# BNO055_MS5838BoB_v02.net
KiCad netlist of a schematic drawn in EAGLE
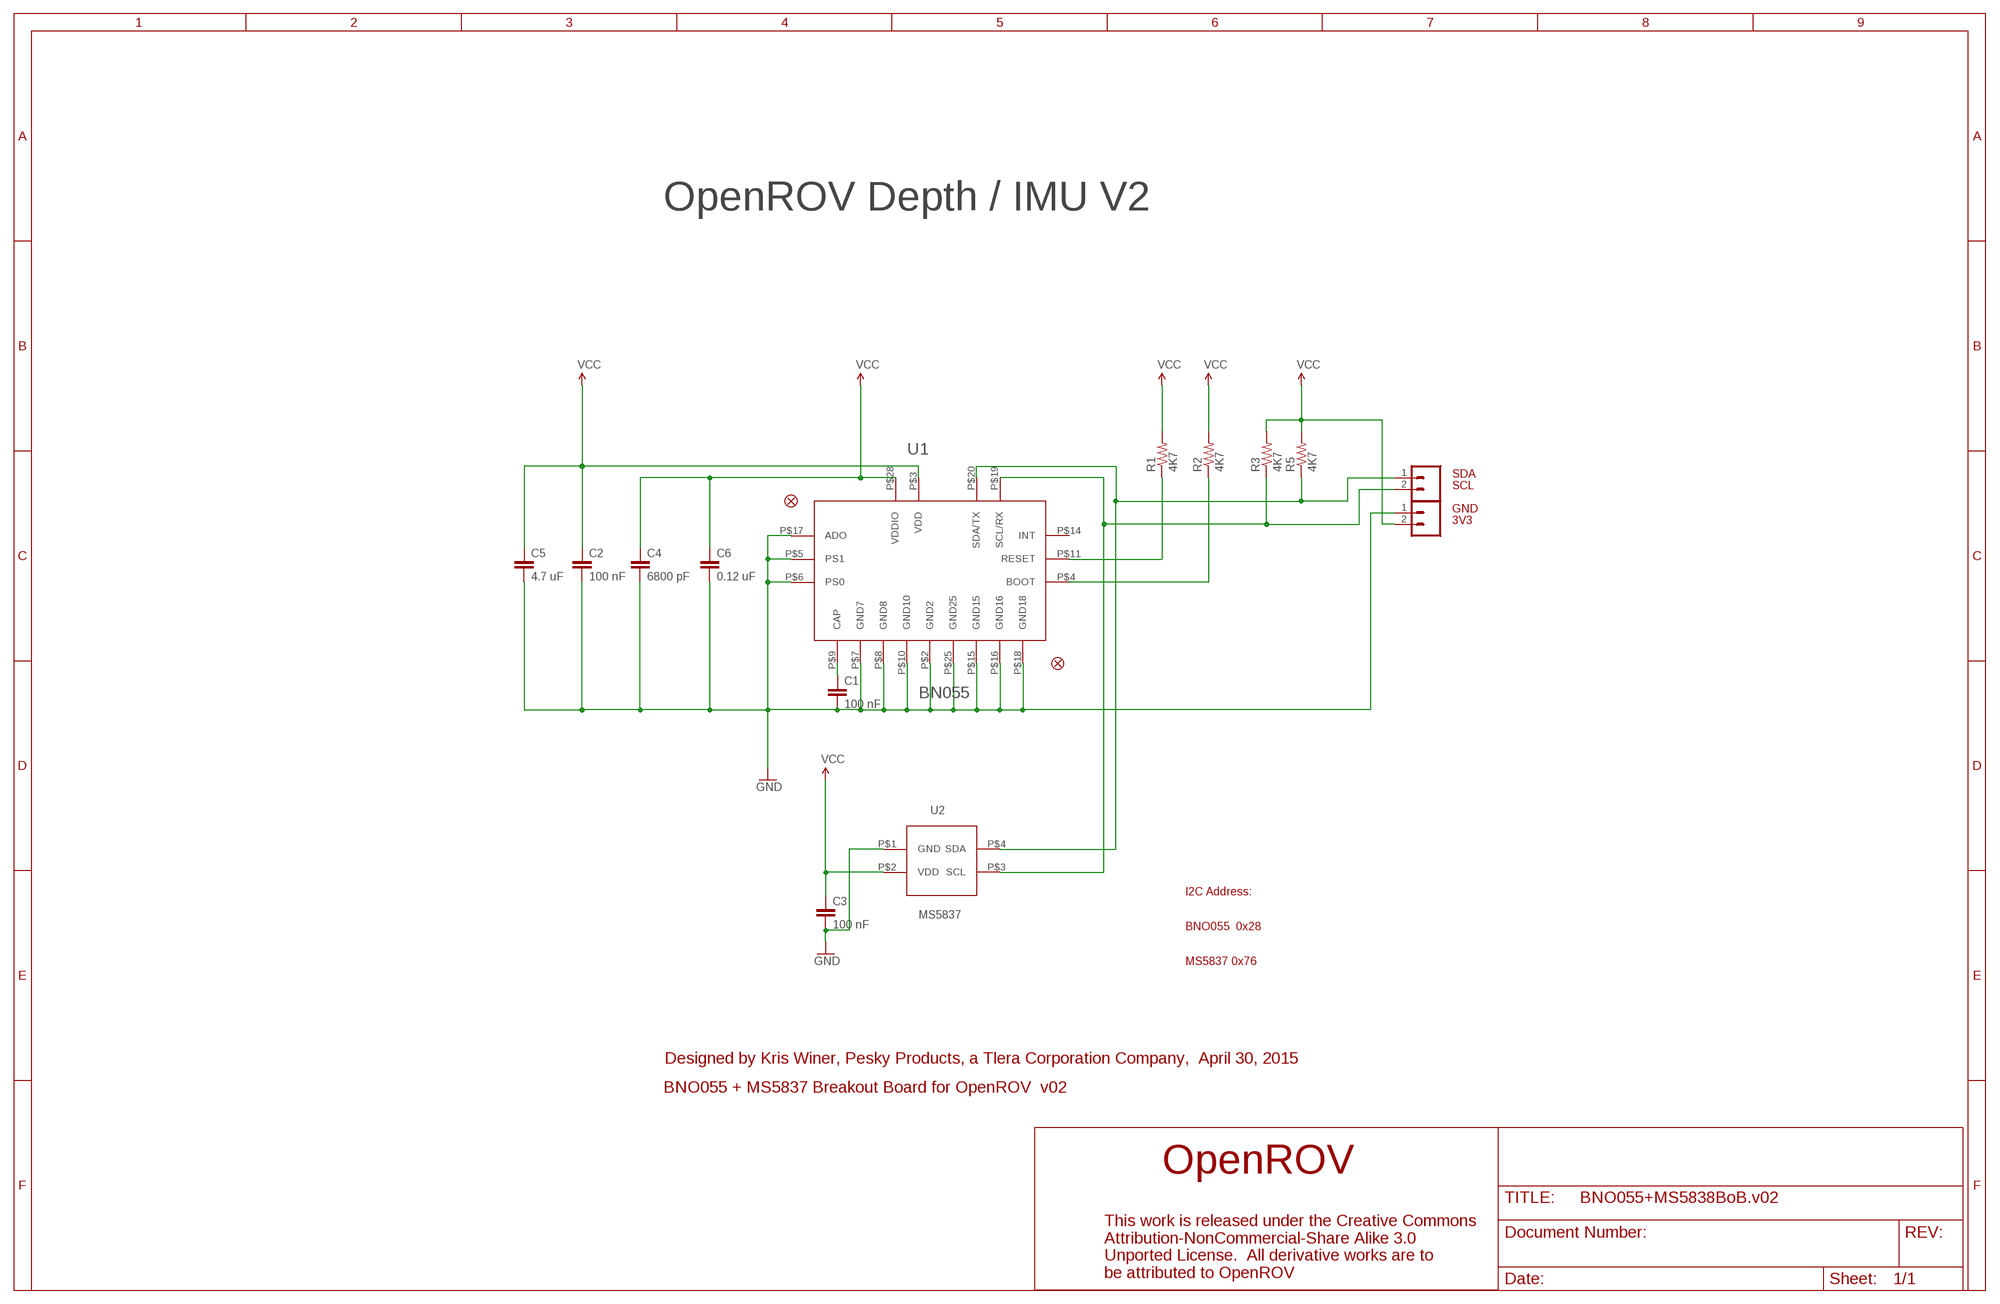
[diagram p0: schematic, sheet 1]

(export (version "E")
  (design (tool "Eeschema 10.0.6"))
  (components
    (comp (ref "C1")
      (value "100 nF")
      (footprint "eagle-import:C0402")
      (libsource (lib "eagle-import") (part "C-EUC0402"))
    )
    (comp (ref "C2")
      (value "100 nF")
      (footprint "eagle-import:C0402")
      (libsource (lib "eagle-import") (part "C-EUC0402"))
    )
    (comp (ref "C3")
      (value "100 nF")
      (footprint "eagle-import:C0402")
      (libsource (lib "eagle-import") (part "C-EUC0402"))
    )
    (comp (ref "C4")
      (value "6800 pF")
      (footprint "eagle-import:C0402")
      (libsource (lib "eagle-import") (part "C-EUC0402"))
    )
    (comp (ref "C5")
      (value "4.7 uF")
      (footprint "eagle-import:C0402")
      (libsource (lib "eagle-import") (part "C-EUC0402"))
    )
    (comp (ref "C6")
      (value "0.12 uF")
      (footprint "eagle-import:C0402")
      (libsource (lib "eagle-import") (part "C-EUC0402"))
    )
    (comp (ref "FID1")
      (value "FIDUCIALUFIDUCIAL")
      (footprint "eagle-import:MICRO-FIDUCIAL")
      (libsource (lib "eagle-import") (part "FIDUCIALUFIDUCIAL"))
    )
    (comp (ref "FID2")
      (value "FIDUCIALUFIDUCIAL")
      (footprint "eagle-import:MICRO-FIDUCIAL")
      (libsource (lib "eagle-import") (part "FIDUCIALUFIDUCIAL"))
    )
    (comp (ref "JP2")
      (value "M021X02_NO_SILK")
      (footprint "eagle-import:1X02_NO_SILK")
      (libsource (lib "eagle-import") (part "M021X02_NO_SILK"))
    )
    (comp (ref "JP3")
      (value "M021X02_NO_SILK")
      (footprint "eagle-import:1X02_NO_SILK")
      (libsource (lib "eagle-import") (part "M021X02_NO_SILK"))
    )
    (comp (ref "R1")
      (value "4K7")
      (footprint "eagle-import:R0402")
      (libsource (lib "eagle-import") (part "R-US_R0402"))
    )
    (comp (ref "R2")
      (value "4K7")
      (footprint "eagle-import:R0402")
      (libsource (lib "eagle-import") (part "R-US_R0402"))
    )
    (comp (ref "R3")
      (value "4K7")
      (footprint "eagle-import:R0402")
      (libsource (lib "eagle-import") (part "R-US_R0402"))
    )
    (comp (ref "R5")
      (value "4K7")
      (footprint "eagle-import:R0402")
      (libsource (lib "eagle-import") (part "R-US_R0402"))
    )
    (comp (ref "U1")
      (value "BN055")
      (footprint "eagle-import:LGA28")
      (libsource (lib "eagle-import") (part "BN055"))
    )
    (comp (ref "U2")
      (value "MS5837")
      (footprint "eagle-import:MS5837")
      (libsource (lib "eagle-import") (part "MS5837"))
    )
  )
  (nets
    (net (code "1") (name "GND") (class "Default")
      (node (ref "C1") (pin "2") (pinfunction "2_2") (pintype "passive"))
      (node (ref "C2") (pin "2") (pinfunction "2_2") (pintype "passive"))
      (node (ref "C3") (pin "2") (pinfunction "2_2") (pintype "passive"))
      (node (ref "C4") (pin "2") (pinfunction "2_2") (pintype "passive"))
      (node (ref "C5") (pin "2") (pinfunction "2_2") (pintype "passive"))
      (node (ref "C6") (pin "2") (pinfunction "2_2") (pintype "passive"))
      (node (ref "JP3") (pin "1") (pinfunction "1_1") (pintype "passive"))
      (node (ref "U1") (pin "P$10") (pinfunction "GND10_P$10") (pintype "power_in"))
      (node (ref "U1") (pin "P$15") (pinfunction "GND15_P$15") (pintype "power_in"))
      (node (ref "U1") (pin "P$16") (pinfunction "GND16_P$16") (pintype "power_in"))
      (node (ref "U1") (pin "P$17") (pinfunction "ADO_P$17") (pintype "bidirectional"))
      (node (ref "U1") (pin "P$18") (pinfunction "GND18_P$18") (pintype "power_in"))
      (node (ref "U1") (pin "P$2") (pinfunction "GND2_P$2") (pintype "power_in"))
      (node (ref "U1") (pin "P$25") (pinfunction "GND25_P$25") (pintype "power_in"))
      (node (ref "U1") (pin "P$5") (pinfunction "PS1_P$5") (pintype "bidirectional"))
      (node (ref "U1") (pin "P$6") (pinfunction "PS0_P$6") (pintype "bidirectional"))
      (node (ref "U1") (pin "P$7") (pinfunction "GND7_P$7") (pintype "power_in"))
      (node (ref "U1") (pin "P$8") (pinfunction "GND8_P$8") (pintype "power_in"))
      (node (ref "U2") (pin "P$1") (pinfunction "GND_P$1") (pintype "bidirectional"))
    )
    (net (code "2") (name "Net-(U1-BOOT)") (class "Default")
      (node (ref "R2") (pin "1") (pinfunction "1_1") (pintype "passive"))
      (node (ref "U1") (pin "P$4") (pinfunction "BOOT_P$4") (pintype "bidirectional"))
    )
    (net (code "3") (name "Net-(U1-CAP)") (class "Default")
      (node (ref "C1") (pin "1") (pinfunction "1_1") (pintype "passive"))
      (node (ref "U1") (pin "P$9") (pinfunction "CAP_P$9") (pintype "power_in"))
    )
    (net (code "4") (name "Net-(U1-RESET)") (class "Default")
      (node (ref "R1") (pin "1") (pinfunction "1_1") (pintype "passive"))
      (node (ref "U1") (pin "P$11") (pinfunction "RESET_P$11") (pintype "bidirectional"))
    )
    (net (code "5") (name "Net-(U1-SCL{slash}RX)") (class "Default")
      (node (ref "JP2") (pin "2") (pinfunction "2_2") (pintype "passive"))
      (node (ref "R3") (pin "1") (pinfunction "1_1") (pintype "passive"))
      (node (ref "U1") (pin "P$19") (pinfunction "SCL/RX_P$19") (pintype "bidirectional"))
      (node (ref "U2") (pin "P$3") (pinfunction "SCL_P$3") (pintype "bidirectional"))
    )
    (net (code "6") (name "Net-(U1-SDA{slash}TX)") (class "Default")
      (node (ref "JP2") (pin "1") (pinfunction "1_1") (pintype "passive"))
      (node (ref "R5") (pin "1") (pinfunction "1_1") (pintype "passive"))
      (node (ref "U1") (pin "P$20") (pinfunction "SDA/TX_P$20") (pintype "bidirectional"))
      (node (ref "U2") (pin "P$4") (pinfunction "SDA_P$4") (pintype "bidirectional"))
    )
    (net (code "7") (name "VCC") (class "Default")
      (node (ref "C2") (pin "1") (pinfunction "1_1") (pintype "passive"))
      (node (ref "C3") (pin "1") (pinfunction "1_1") (pintype "passive"))
      (node (ref "C4") (pin "1") (pinfunction "1_1") (pintype "passive"))
      (node (ref "C5") (pin "1") (pinfunction "1_1") (pintype "passive"))
      (node (ref "C6") (pin "1") (pinfunction "1_1") (pintype "passive"))
      (node (ref "JP3") (pin "2") (pinfunction "2_2") (pintype "passive"))
      (node (ref "R1") (pin "2") (pinfunction "2_2") (pintype "passive"))
      (node (ref "R2") (pin "2") (pinfunction "2_2") (pintype "passive"))
      (node (ref "R3") (pin "2") (pinfunction "2_2") (pintype "passive"))
      (node (ref "R5") (pin "2") (pinfunction "2_2") (pintype "passive"))
      (node (ref "U1") (pin "P$28") (pinfunction "VDDIO_P$28") (pintype "power_in"))
      (node (ref "U1") (pin "P$3") (pinfunction "VDD_P$3") (pintype "power_in"))
      (node (ref "U2") (pin "P$2") (pinfunction "VDD_P$2") (pintype "bidirectional"))
    )
    (net (code "8") (name "unconnected-(U1-INT-PadP$14)") (class "Default")
      (node (ref "U1") (pin "P$14") (pinfunction "INT_P$14") (pintype "bidirectional"))
    )
  )
)
